# ADC_Isolation.net
KiCad netlist of a schematic drawn in Altium Designer
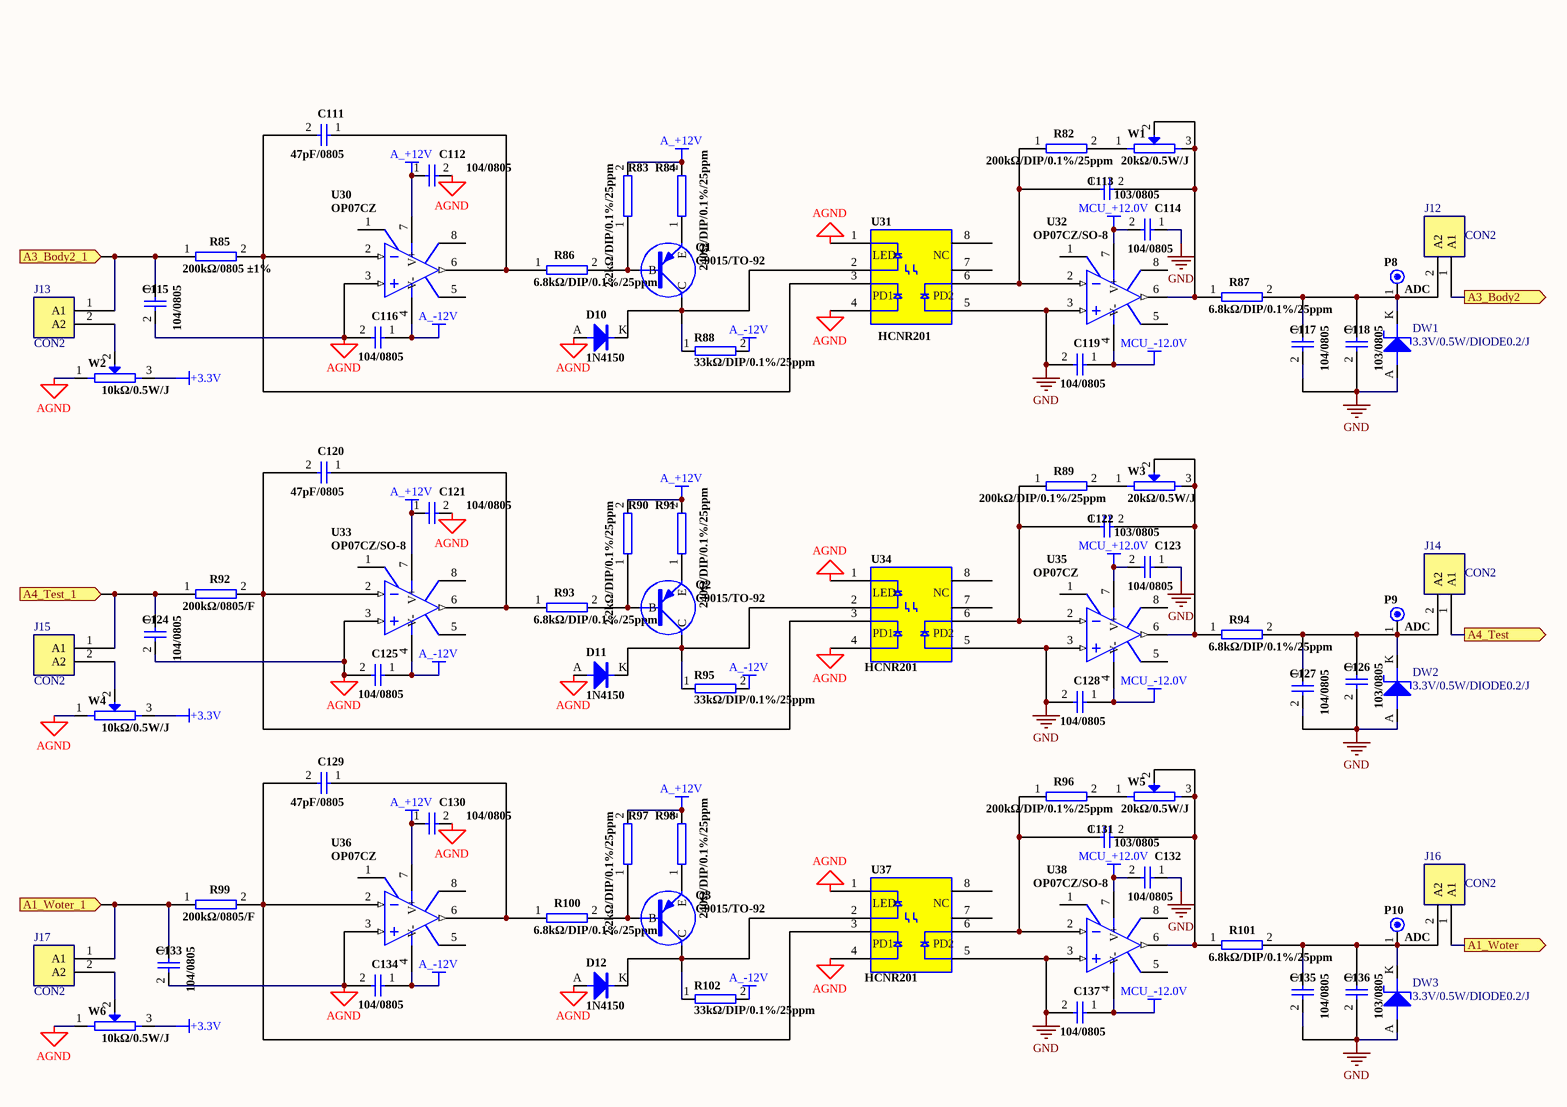
[diagram p0: ADC_Isolation.SchDoc]

(export (version "E")
  (design (tool "Eeschema 10.0.6"))
  (components
    (comp (ref "C111")
      (value "47pF/0805")
      (footprint "C0805")
      (description "贴片电容 47pF/25V ±1% C0805")
      (libsource (lib "") (part "CAP_1"))
    )
    (comp (ref "C112")
      (value "104/0805")
      (footprint "C0805")
      (description "贴片电容 104/25V ±1% C0805")
      (libsource (lib "") (part "CAP_1"))
    )
    (comp (ref "C113")
      (value "103/0805")
      (footprint "C0805")
      (description "贴片电容 103/25V ±1% C0805")
      (libsource (lib "") (part "CAP_1"))
    )
    (comp (ref "C114")
      (value "104/0805")
      (footprint "C0805")
      (description "贴片电容 104/25V ±1% C0805")
      (libsource (lib "") (part "CAP_1"))
    )
    (comp (ref "C115")
      (value "104/0805")
      (footprint "C0805")
      (description "贴片电容 104/25V ±1% C0805")
      (libsource (lib "COOLCONTROL") (part "CAP"))
    )
    (comp (ref "C116")
      (value "104/0805")
      (footprint "COOLCONTROL:C0805")
      (description "贴片电容 104/25V ±1% C0805")
      (libsource (lib "") (part "CAP_1"))
    )
    (comp (ref "C117")
      (value "104/0805")
      (footprint "C0805")
      (description "贴片电容 104/25V ±1% C0805")
      (libsource (lib "COOLCONTROL") (part "CAP"))
    )
    (comp (ref "C118")
      (value "103/0805")
      (footprint "C0805")
      (description "贴片电容 103/25V ±1% C0805")
      (libsource (lib "COOLCONTROL") (part "CAP"))
    )
    (comp (ref "C119")
      (value "104/0805")
      (footprint "C0805")
      (description "贴片电容 104/25V ±1% C0805")
      (libsource (lib "") (part "CAP_1"))
    )
    (comp (ref "C120")
      (value "47pF/0805")
      (footprint "C0805")
      (description "贴片电容 47pF/25V ±1% C0805")
      (libsource (lib "") (part "CAP_1"))
    )
    (comp (ref "C121")
      (value "104/0805")
      (footprint "C0805")
      (description "贴片电容 104/25V ±1% C0805")
      (libsource (lib "") (part "CAP_1"))
    )
    (comp (ref "C122")
      (value "103/0805")
      (footprint "C0805")
      (description "贴片电容 103/25V ±1% C0805")
      (libsource (lib "") (part "CAP_1"))
    )
    (comp (ref "C123")
      (value "104/0805")
      (footprint "C0805")
      (description "贴片电容 104/25V ±1% C0805")
      (libsource (lib "") (part "CAP_1"))
    )
    (comp (ref "C124")
      (value "104/0805")
      (footprint "C0805")
      (description "贴片电容 104/25V ±1% C0805")
      (libsource (lib "COOLCONTROL") (part "CAP"))
    )
    (comp (ref "C125")
      (value "104/0805")
      (footprint "C0805")
      (description "贴片电容 104/25V ±1% C0805")
      (libsource (lib "") (part "CAP_1"))
    )
    (comp (ref "C126")
      (value "103/0805")
      (footprint "COOLCONTROL:C0805")
      (description "贴片电容 103/25V ±1% C0805")
      (libsource (lib "COOLCONTROL") (part "CAP"))
    )
    (comp (ref "C127")
      (value "104/0805")
      (footprint "C0805")
      (description "贴片电容 104/25V ±1% C0805")
      (libsource (lib "COOLCONTROL") (part "CAP"))
    )
    (comp (ref "C128")
      (value "104/0805")
      (footprint "C0805")
      (description "贴片电容 104/25V ±1% C0805")
      (libsource (lib "") (part "CAP_1"))
    )
    (comp (ref "C129")
      (value "47pF/0805")
      (footprint "C0805")
      (description "贴片电容 47pF/25V ±1% C0805")
      (libsource (lib "") (part "CAP_1"))
    )
    (comp (ref "C130")
      (value "104/0805")
      (footprint "C0805")
      (description "贴片电容 104/25V ±1% C0805")
      (libsource (lib "") (part "CAP_1"))
    )
    (comp (ref "C131")
      (value "103/0805")
      (footprint "C0805")
      (description "贴片电容 103/25V ±1% C0805")
      (libsource (lib "") (part "CAP_1"))
    )
    (comp (ref "C132")
      (value "104/0805")
      (footprint "C0805")
      (description "贴片电容 104/25V ±1% C0805")
      (libsource (lib "") (part "CAP_1"))
    )
    (comp (ref "C133")
      (value "104/0805")
      (footprint "C0805")
      (description "贴片电容 104/25V ±1% C0805")
      (libsource (lib "COOLCONTROL") (part "CAP"))
    )
    (comp (ref "C134")
      (value "104/0805")
      (footprint "C0805")
      (description "贴片电容 104/25V ±1% C0805")
      (libsource (lib "") (part "CAP_1"))
    )
    (comp (ref "C135")
      (value "104/0805")
      (footprint "C0805")
      (description "贴片电容 104/25V ±1% C0805")
      (libsource (lib "COOLCONTROL") (part "CAP"))
    )
    (comp (ref "C136")
      (value "103/0805")
      (footprint "COOLCONTROL:C0805")
      (description "贴片电容 103/25V ±1% C0805")
      (libsource (lib "COOLCONTROL") (part "CAP"))
    )
    (comp (ref "C137")
      (value "104/0805")
      (footprint "C0805")
      (description "贴片电容 104/25V ±1% C0805")
      (libsource (lib "") (part "CAP_1"))
    )
    (comp (ref "D10")
      (value "1N4150")
      (footprint "DIODE0.2")
      (description "快速开关二极管 1N415050V 450mA/J /DIODE0.2")
      (libsource (lib "COOLCONTROL") (part "DIODE0"))
    )
    (comp (ref "D11")
      (value "1N4150")
      (footprint "DIODE0.2")
      (description "快速开关二极管 1N415050V 450mA/J /DIODE0.2")
      (libsource (lib "COOLCONTROL") (part "DIODE0"))
    )
    (comp (ref "D12")
      (value "1N4150")
      (footprint "DIODE0.2")
      (description "快速开关二极管 1N415050V 450mA/J /DIODE0.2")
      (libsource (lib "COOLCONTROL") (part "DIODE0"))
    )
    (comp (ref "DW1")
      (value "3.3V/0.5W/DIODE0.2/J")
      (footprint "DIODE0.2")
      (description "稳压二极管 3.3V/0.5W/DIODE0.2/J")
      (libsource (lib "COOLCONTROL") (part "ZENER0"))
    )
    (comp (ref "DW2")
      (value "3.3V/0.5W/DIODE0.2/J")
      (footprint "DIODE0.2")
      (description "稳压二极管 3.3V/0.5W/DIODE0.2/J")
      (libsource (lib "COOLCONTROL") (part "ZENER0"))
    )
    (comp (ref "DW3")
      (value "3.3V/0.5W/DIODE0.2/J")
      (footprint "DIODE0.2")
      (description "稳压二极管 3.3V/0.5W/DIODE0.2/J")
      (libsource (lib "COOLCONTROL") (part "ZENER0"))
    )
    (comp (ref "J12")
      (value "CON2")
      (footprint "COOLCONTROL:2Pin-2.54")
      (description "单排排针（2针）2.54mm 2Pin-2.54")
      (libsource (lib "COOLCONTROL") (part "CON2"))
    )
    (comp (ref "J13")
      (value "CON2")
      (footprint "COOLCONTROL:2Pin-2.54")
      (description "单排排针（2针）2.54mm 2Pin-2.54")
      (libsource (lib "") (part "CON2_1"))
    )
    (comp (ref "J14")
      (value "CON2")
      (footprint "COOLCONTROL:2Pin-2.54")
      (description "单排排针（2针）2.54mm 2Pin-2.54")
      (libsource (lib "COOLCONTROL") (part "CON2"))
    )
    (comp (ref "J15")
      (value "CON2")
      (footprint "COOLCONTROL:2Pin-2.54")
      (description "单排排针（2针）2.54mm 2Pin-2.54")
      (libsource (lib "") (part "CON2_1"))
    )
    (comp (ref "J16")
      (value "CON2")
      (footprint "COOLCONTROL:2Pin-2.54")
      (description "单排排针（2针）2.54mm 2Pin-2.54")
      (libsource (lib "COOLCONTROL") (part "CON2"))
    )
    (comp (ref "J17")
      (value "CON2")
      (footprint "COOLCONTROL:2Pin-2.54")
      (description "单排排针（2针）2.54mm 2Pin-2.54")
      (libsource (lib "") (part "CON2_1"))
    )
    (comp (ref "P8") (value "ADC") (footprint "TESTSMD") (libsource (lib "COOLCONTROL") (part "CON1")))
    (comp (ref "P9") (value "ADC") (footprint "TESTSMD") (libsource (lib "COOLCONTROL") (part "CON1")))
    (comp (ref "P10") (value "ADC") (footprint "TESTSMD") (libsource (lib "COOLCONTROL") (part "CON1")))
    (comp (ref "Q1")
      (value "C9015/TO-92")
      (footprint "COOLCONTROL:TO-92")
      (description "三极管 C9015 TO-92")
      (libsource (lib "COOLCONTROL") (part "PNP"))
    )
    (comp (ref "Q2")
      (value "C9015/TO-92")
      (footprint "COOLCONTROL:TO-92")
      (description "三极管 C9015 TO-92")
      (libsource (lib "COOLCONTROL") (part "PNP"))
    )
    (comp (ref "Q3")
      (value "C9015/TO-92")
      (footprint "COOLCONTROL:TO-92")
      (description "三极管 C9015 TO-92")
      (libsource (lib "COOLCONTROL") (part "PNP"))
    )
    (comp (ref "R82")
      (value "200kΩ/DIP/0.1%/25ppm")
      (footprint "AXIAL0.4")
      (description "高精度电阻 200kΩ DIP ±0.1% 25ppm AXIAL0.4")
      (libsource (lib "COOLCONTROL") (part "RES2"))
    )
    (comp (ref "R83")
      (value "2.2kΩ/DIP/0.1%/25ppm")
      (footprint "AXIAL0.4")
      (description "高精度电阻 2.2kΩ DIP ±0.1% 25ppm AXIAL0.4")
      (libsource (lib "COOLCONTROL") (part "RES2"))
    )
    (comp (ref "R84")
      (value "240Ω/DIP/0.1%/25ppm")
      (footprint "AXIAL0.4")
      (description "高精度电阻 240Ω DIP ±0.1% 25ppm AXIAL0.4")
      (libsource (lib "COOLCONTROL") (part "RES2"))
    )
    (comp (ref "R85")
      (value "200kΩ/0805 ±1%")
      (footprint "R0805")
      (description "贴片电阻 200kΩ 0.25W ±1% R0805")
      (libsource (lib "COOLCONTROL") (part "RES2"))
    )
    (comp (ref "R86")
      (value "6.8kΩ/DIP/0.1%/25ppm")
      (footprint "AXIAL0.4")
      (description "高精度电阻 6.8kΩ DIP ±0.1% 25ppm AXIAL0.4")
      (libsource (lib "COOLCONTROL") (part "RES2"))
    )
    (comp (ref "R87")
      (value "6.8kΩ/DIP/0.1%/25ppm")
      (footprint "AXIAL0.4")
      (description "高精度电阻 6.8kΩ DIP ±0.1% 25ppm AXIAL0.4")
      (libsource (lib "COOLCONTROL") (part "RES2"))
    )
    (comp (ref "R88")
      (value "33kΩ/DIP/0.1%/25ppm")
      (footprint "AXIAL0.4")
      (description "高精度电阻 33kΩ DIP ±0.1% 25ppm AXIAL0.4")
      (libsource (lib "COOLCONTROL") (part "RES2"))
    )
    (comp (ref "R89")
      (value "200kΩ/DIP/0.1%/25ppm")
      (footprint "AXIAL0.4")
      (description "高精度电阻 200kΩ DIP ±0.1% 25ppm AXIAL0.4")
      (libsource (lib "COOLCONTROL") (part "RES2"))
    )
    (comp (ref "R90")
      (value "2.2kΩ/DIP/0.1%/25ppm")
      (footprint "AXIAL0.4")
      (description "高精度电阻 2.2kΩ DIP ±0.1% 25ppm AXIAL0.4")
      (libsource (lib "COOLCONTROL") (part "RES2"))
    )
    (comp (ref "R91")
      (value "240Ω/DIP/0.1%/25ppm")
      (footprint "AXIAL0.4")
      (description "高精度电阻 240Ω DIP ±0.1% 25ppm AXIAL0.4")
      (libsource (lib "COOLCONTROL") (part "RES2"))
    )
    (comp (ref "R92")
      (value "200kΩ/0805/F")
      (footprint "R0805")
      (description "贴片电阻 200kΩ 0.25W ±1% R0805")
      (libsource (lib "COOLCONTROL") (part "RES2"))
    )
    (comp (ref "R93")
      (value "6.8kΩ/DIP/0.1%/25ppm")
      (footprint "AXIAL0.4")
      (description "高精度电阻 6.8kΩ DIP ±0.1% 25ppm AXIAL0.4")
      (libsource (lib "COOLCONTROL") (part "RES2"))
    )
    (comp (ref "R94")
      (value "6.8kΩ/DIP/0.1%/25ppm")
      (footprint "COOLCONTROL:AXIAL0.4")
      (description "高精度电阻 6.8kΩ DIP ±0.1% 25ppm AXIAL0.4")
      (libsource (lib "COOLCONTROL") (part "RES2"))
    )
    (comp (ref "R95")
      (value "33kΩ/DIP/0.1%/25ppm")
      (footprint "AXIAL0.4")
      (description "高精度电阻 33kΩ DIP ±0.1% 25ppm AXIAL0.4")
      (libsource (lib "COOLCONTROL") (part "RES2"))
    )
    (comp (ref "R96")
      (value "200kΩ/DIP/0.1%/25ppm")
      (footprint "AXIAL0.4")
      (description "高精度电阻 200kΩ DIP ±0.1% 25ppm AXIAL0.4")
      (libsource (lib "COOLCONTROL") (part "RES2"))
    )
    (comp (ref "R97")
      (value "2.2kΩ/DIP/0.1%/25ppm")
      (footprint "AXIAL0.4")
      (description "高精度电阻 2.2kΩ DIP ±0.1% 25ppm AXIAL0.4")
      (libsource (lib "COOLCONTROL") (part "RES2"))
    )
    (comp (ref "R98")
      (value "240Ω/DIP/0.1%/25ppm")
      (footprint "AXIAL0.4")
      (description "高精度电阻 240Ω DIP ±0.1% 25ppm AXIAL0.4")
      (libsource (lib "COOLCONTROL") (part "RES2"))
    )
    (comp (ref "R99")
      (value "200kΩ/0805/F")
      (footprint "R0805")
      (description "贴片电阻 200kΩ 0.25W ±1% R0805")
      (libsource (lib "COOLCONTROL") (part "RES2"))
    )
    (comp (ref "R100")
      (value "6.8kΩ/DIP/0.1%/25ppm")
      (footprint "AXIAL0.4")
      (description "高精度电阻 6.8kΩ DIP ±0.1% 25ppm AXIAL0.4")
      (libsource (lib "COOLCONTROL") (part "RES2"))
    )
    (comp (ref "R101")
      (value "6.8kΩ/DIP/0.1%/25ppm")
      (footprint "AXIAL0.4")
      (description "高精度电阻 6.8kΩ DIP ±0.1% 25ppm AXIAL0.4")
      (libsource (lib "COOLCONTROL") (part "RES2"))
    )
    (comp (ref "R102")
      (value "33kΩ/DIP/0.1%/25ppm")
      (footprint "AXIAL0.4")
      (description "高精度电阻 33kΩ DIP ±0.1% 25ppm AXIAL0.4")
      (libsource (lib "COOLCONTROL") (part "RES2"))
    )
    (comp (ref "U30")
      (value "OP07CZ")
      (footprint "SO-8")
      (description "运算放大器 OP07CZ SO-8")
      (libsource (lib "COOLCONTROL") (part "OP07CZ"))
    )
    (comp (ref "U31")
      (value "HCNR201")
      (footprint "DIP08W")
      (description "线性光耦隔离器 HCNR201 DIP08W")
      (libsource (lib "COOLCONTROL") (part "HCNR201"))
    )
    (comp (ref "U32")
      (value "OP07CZ/SO-8")
      (footprint "SO-8")
      (description "运算放大器 OP07CZ SO-8")
      (libsource (lib "COOLCONTROL") (part "OP07CZ"))
    )
    (comp (ref "U33")
      (value "OP07CZ/SO-8")
      (footprint "SO-8")
      (description "运算放大器 OP07CZ SO-8")
      (libsource (lib "COOLCONTROL") (part "OP07CZ"))
    )
    (comp (ref "U34")
      (value "HCNR201")
      (footprint "DIP08W")
      (description "线性光耦隔离器 HCNR201 DIP08W")
      (libsource (lib "COOLCONTROL") (part "HCNR201"))
    )
    (comp (ref "U35")
      (value "OP07CZ")
      (footprint "SO-8")
      (description "运算放大器 OP07CZ SO-8")
      (libsource (lib "COOLCONTROL") (part "OP07CZ"))
    )
    (comp (ref "U36")
      (value "OP07CZ")
      (footprint "SO-8")
      (description "运算放大器 OP07CZ SO-8")
      (libsource (lib "COOLCONTROL") (part "OP07CZ"))
    )
    (comp (ref "U37")
      (value "HCNR201")
      (footprint "DIP08W")
      (description "线性光耦隔离器 HCNR201 DIP08W")
      (libsource (lib "COOLCONTROL") (part "HCNR201"))
    )
    (comp (ref "U38")
      (value "OP07CZ/SO-8")
      (footprint "SO-8")
      (description "运算放大器 OP07CZ SO-8")
      (libsource (lib "COOLCONTROL") (part "OP07CZ"))
    )
    (comp (ref "W1")
      (value "20kΩ/0.5W/J")
      (footprint "3224W")
      (description "高精密可调电位器 20kΩ/0.5W/J  3224W")
      (libsource (lib "COOLCONTROL") (part "RPOT"))
    )
    (comp (ref "W2")
      (value "10kΩ/0.5W/J")
      (footprint "3224W")
      (description "高精密可调电位器 10kΩ/0.5W/J  3224W")
      (libsource (lib "COOLCONTROL") (part "RPOT"))
    )
    (comp (ref "W3")
      (value "20kΩ/0.5W/J")
      (footprint "3224W")
      (description "高精密可调电位器 20kΩ/0.5W/J  3224W")
      (libsource (lib "COOLCONTROL") (part "RPOT"))
    )
    (comp (ref "W4")
      (value "10kΩ/0.5W/J")
      (footprint "3224W")
      (description "高精密可调电位器 10kΩ/0.5W/J  3224W")
      (libsource (lib "COOLCONTROL") (part "RPOT"))
    )
    (comp (ref "W5")
      (value "20kΩ/0.5W/J")
      (footprint "3224W")
      (description "高精密可调电位器 20kΩ/0.5W/J  3224W")
      (libsource (lib "COOLCONTROL") (part "RPOT"))
    )
    (comp (ref "W6")
      (value "10kΩ/0.5W/J")
      (footprint "3224W")
      (description "高精密可调电位器 10kΩ/0.5W/J  3224W")
      (libsource (lib "COOLCONTROL") (part "RPOT"))
    )
  )
  (nets
    (net (code "1") (name "+3.3V") (class "Default")
      (node (ref "W2") (pin "3") (pintype "passive"))
      (node (ref "W4") (pin "3") (pintype "passive"))
      (node (ref "W6") (pin "3") (pintype "passive"))
    )
    (net (code "2") (name "/A1_Woter") (class "Default")
      (node (ref "J16") (pin "1") (pinfunction "A1_1") (pintype "passive"))
    )
    (net (code "3") (name "/A1_Woter_1") (class "Default")
      (node (ref "C133") (pin "1") (pintype "passive"))
      (node (ref "J17") (pin "1") (pinfunction "A1_1") (pintype "passive"))
      (node (ref "R99") (pin "1") (pintype "passive"))
    )
    (net (code "4") (name "/A3_Body2") (class "Default")
      (node (ref "J12") (pin "1") (pinfunction "A1_1") (pintype "passive"))
    )
    (net (code "5") (name "/A3_Body2_1") (class "Default")
      (node (ref "C115") (pin "1") (pintype "passive"))
      (node (ref "J13") (pin "1") (pinfunction "A1_1") (pintype "passive"))
      (node (ref "R85") (pin "1") (pintype "passive"))
    )
    (net (code "6") (name "/A4_Test") (class "Default")
      (node (ref "J14") (pin "1") (pinfunction "A1_1") (pintype "passive"))
    )
    (net (code "7") (name "/A4_Test_1") (class "Default")
      (node (ref "C124") (pin "1") (pintype "passive"))
      (node (ref "J15") (pin "1") (pinfunction "A1_1") (pintype "passive"))
      (node (ref "R92") (pin "1") (pintype "passive"))
    )
    (net (code "8") (name "AGND") (class "Default")
      (node (ref "C112") (pin "2") (pintype "passive"))
      (node (ref "C115") (pin "2") (pintype "passive"))
      (node (ref "C116") (pin "2") (pintype "passive"))
      (node (ref "C121") (pin "2") (pintype "passive"))
      (node (ref "C124") (pin "2") (pintype "passive"))
      (node (ref "C125") (pin "2") (pintype "passive"))
      (node (ref "C130") (pin "2") (pintype "passive"))
      (node (ref "C133") (pin "2") (pintype "passive"))
      (node (ref "C134") (pin "2") (pintype "passive"))
      (node (ref "D10") (pin "A") (pintype "passive"))
      (node (ref "D11") (pin "A") (pintype "passive"))
      (node (ref "D12") (pin "A") (pintype "passive"))
      (node (ref "U30") (pin "3") (pintype "input"))
      (node (ref "U31") (pin "1") (pintype "passive"))
      (node (ref "U31") (pin "4") (pintype "passive"))
      (node (ref "U33") (pin "3") (pintype "input"))
      (node (ref "U34") (pin "1") (pintype "passive"))
      (node (ref "U34") (pin "4") (pintype "passive"))
      (node (ref "U36") (pin "3") (pintype "input"))
      (node (ref "U37") (pin "1") (pintype "passive"))
      (node (ref "U37") (pin "4") (pintype "passive"))
      (node (ref "W2") (pin "1") (pintype "passive"))
      (node (ref "W4") (pin "1") (pintype "passive"))
      (node (ref "W6") (pin "1") (pintype "passive"))
    )
    (net (code "9") (name "A_+12V") (class "Default")
      (node (ref "C112") (pin "1") (pintype "passive"))
      (node (ref "C121") (pin "1") (pintype "passive"))
      (node (ref "C130") (pin "1") (pintype "passive"))
      (node (ref "R83") (pin "2") (pintype "passive"))
      (node (ref "R84") (pin "2") (pintype "passive"))
      (node (ref "R90") (pin "2") (pintype "passive"))
      (node (ref "R91") (pin "2") (pintype "passive"))
      (node (ref "R97") (pin "2") (pintype "passive"))
      (node (ref "R98") (pin "2") (pintype "passive"))
      (node (ref "U30") (pin "7") (pinfunction "V+_7") (pintype "power_in"))
      (node (ref "U33") (pin "7") (pinfunction "V+_7") (pintype "power_in"))
      (node (ref "U36") (pin "7") (pinfunction "V+_7") (pintype "power_in"))
    )
    (net (code "10") (name "A_-12V") (class "Default")
      (node (ref "C116") (pin "1") (pintype "passive"))
      (node (ref "C125") (pin "1") (pintype "passive"))
      (node (ref "C134") (pin "1") (pintype "passive"))
      (node (ref "R102") (pin "2") (pintype "passive"))
      (node (ref "R88") (pin "2") (pintype "passive"))
      (node (ref "R95") (pin "2") (pintype "passive"))
      (node (ref "U30") (pin "4") (pinfunction "V-_4") (pintype "power_in"))
      (node (ref "U33") (pin "4") (pinfunction "V-_4") (pintype "power_in"))
      (node (ref "U36") (pin "4") (pinfunction "V-_4") (pintype "power_in"))
    )
    (net (code "11") (name "GND") (class "Default")
      (node (ref "C114") (pin "1") (pintype "passive"))
      (node (ref "C117") (pin "2") (pintype "passive"))
      (node (ref "C118") (pin "2") (pintype "passive"))
      (node (ref "C119") (pin "2") (pintype "passive"))
      (node (ref "C123") (pin "1") (pintype "passive"))
      (node (ref "C126") (pin "2") (pintype "passive"))
      (node (ref "C127") (pin "2") (pintype "passive"))
      (node (ref "C128") (pin "2") (pintype "passive"))
      (node (ref "C132") (pin "1") (pintype "passive"))
      (node (ref "C135") (pin "2") (pintype "passive"))
      (node (ref "C136") (pin "2") (pintype "passive"))
      (node (ref "C137") (pin "2") (pintype "passive"))
      (node (ref "DW1") (pin "A") (pintype "passive"))
      (node (ref "DW2") (pin "A") (pintype "passive"))
      (node (ref "DW3") (pin "A") (pintype "passive"))
      (node (ref "U31") (pin "5") (pintype "passive"))
      (node (ref "U32") (pin "3") (pintype "input"))
      (node (ref "U34") (pin "5") (pintype "passive"))
      (node (ref "U35") (pin "3") (pintype "input"))
      (node (ref "U37") (pin "5") (pintype "passive"))
      (node (ref "U38") (pin "3") (pintype "input"))
    )
    (net (code "12") (name "MCU_+12.0V") (class "Default")
      (node (ref "C114") (pin "2") (pintype "passive"))
      (node (ref "C123") (pin "2") (pintype "passive"))
      (node (ref "C132") (pin "2") (pintype "passive"))
      (node (ref "U32") (pin "7") (pinfunction "V+_7") (pintype "power_in"))
      (node (ref "U35") (pin "7") (pinfunction "V+_7") (pintype "power_in"))
      (node (ref "U38") (pin "7") (pinfunction "V+_7") (pintype "power_in"))
    )
    (net (code "13") (name "MCU_-12.0V") (class "Default")
      (node (ref "C119") (pin "1") (pintype "passive"))
      (node (ref "C128") (pin "1") (pintype "passive"))
      (node (ref "C137") (pin "1") (pintype "passive"))
      (node (ref "U32") (pin "4") (pinfunction "V-_4") (pintype "power_in"))
      (node (ref "U35") (pin "4") (pinfunction "V-_4") (pintype "power_in"))
      (node (ref "U38") (pin "4") (pinfunction "V-_4") (pintype "power_in"))
    )
    (net (code "14") (name "Net-(C111-Pad1)") (class "Default")
      (node (ref "C111") (pin "1") (pintype "passive"))
      (node (ref "R86") (pin "1") (pintype "passive"))
      (node (ref "U30") (pin "6") (pintype "output"))
    )
    (net (code "15") (name "Net-(C111-Pad2)") (class "Default")
      (node (ref "C111") (pin "2") (pintype "passive"))
      (node (ref "R85") (pin "2") (pintype "passive"))
      (node (ref "U30") (pin "2") (pintype "input"))
      (node (ref "U31") (pin "3") (pintype "passive"))
    )
    (net (code "16") (name "Net-(C113-Pad1)") (class "Default")
      (node (ref "C113") (pin "1") (pintype "passive"))
      (node (ref "R82") (pin "1") (pintype "passive"))
      (node (ref "U31") (pin "6") (pintype "passive"))
      (node (ref "U32") (pin "2") (pintype "input"))
    )
    (net (code "17") (name "Net-(C113-Pad2)") (class "Default")
      (node (ref "C113") (pin "2") (pintype "passive"))
      (node (ref "R87") (pin "1") (pintype "passive"))
      (node (ref "U32") (pin "6") (pintype "output"))
      (node (ref "W1") (pin "2") (pintype "passive"))
      (node (ref "W1") (pin "3") (pintype "passive"))
    )
    (net (code "18") (name "Net-(C120-Pad1)") (class "Default")
      (node (ref "C120") (pin "1") (pintype "passive"))
      (node (ref "R93") (pin "1") (pintype "passive"))
      (node (ref "U33") (pin "6") (pintype "output"))
    )
    (net (code "19") (name "Net-(C120-Pad2)") (class "Default")
      (node (ref "C120") (pin "2") (pintype "passive"))
      (node (ref "R92") (pin "2") (pintype "passive"))
      (node (ref "U33") (pin "2") (pintype "input"))
      (node (ref "U34") (pin "3") (pintype "passive"))
    )
    (net (code "20") (name "Net-(C122-Pad1)") (class "Default")
      (node (ref "C122") (pin "1") (pintype "passive"))
      (node (ref "R89") (pin "1") (pintype "passive"))
      (node (ref "U34") (pin "6") (pintype "passive"))
      (node (ref "U35") (pin "2") (pintype "input"))
    )
    (net (code "21") (name "Net-(C122-Pad2)") (class "Default")
      (node (ref "C122") (pin "2") (pintype "passive"))
      (node (ref "R94") (pin "1") (pintype "passive"))
      (node (ref "U35") (pin "6") (pintype "output"))
      (node (ref "W3") (pin "2") (pintype "passive"))
      (node (ref "W3") (pin "3") (pintype "passive"))
    )
    (net (code "22") (name "Net-(C129-Pad1)") (class "Default")
      (node (ref "C129") (pin "1") (pintype "passive"))
      (node (ref "R100") (pin "1") (pintype "passive"))
      (node (ref "U36") (pin "6") (pintype "output"))
    )
    (net (code "23") (name "Net-(C129-Pad2)") (class "Default")
      (node (ref "C129") (pin "2") (pintype "passive"))
      (node (ref "R99") (pin "2") (pintype "passive"))
      (node (ref "U36") (pin "2") (pintype "input"))
      (node (ref "U37") (pin "3") (pintype "passive"))
    )
    (net (code "24") (name "Net-(C131-Pad1)") (class "Default")
      (node (ref "C131") (pin "1") (pintype "passive"))
      (node (ref "R96") (pin "1") (pintype "passive"))
      (node (ref "U37") (pin "6") (pintype "passive"))
      (node (ref "U38") (pin "2") (pintype "input"))
    )
    (net (code "25") (name "Net-(C131-Pad2)") (class "Default")
      (node (ref "C131") (pin "2") (pintype "passive"))
      (node (ref "R101") (pin "1") (pintype "passive"))
      (node (ref "U38") (pin "6") (pintype "output"))
      (node (ref "W5") (pin "2") (pintype "passive"))
      (node (ref "W5") (pin "3") (pintype "passive"))
    )
    (net (code "26") (name "Net-(J12-A2)") (class "Default")
      (node (ref "C117") (pin "1") (pintype "passive"))
      (node (ref "C118") (pin "1") (pintype "passive"))
      (node (ref "DW1") (pin "K") (pintype "passive"))
      (node (ref "J12") (pin "2") (pinfunction "A2_2") (pintype "passive"))
      (node (ref "P8") (pin "1") (pintype "passive"))
      (node (ref "R87") (pin "2") (pintype "passive"))
    )
    (net (code "27") (name "Net-(J13-A2)") (class "Default")
      (node (ref "J13") (pin "2") (pinfunction "A2_2") (pintype "passive"))
      (node (ref "W2") (pin "2") (pintype "passive"))
    )
    (net (code "28") (name "Net-(J14-A2)") (class "Default")
      (node (ref "C126") (pin "1") (pintype "passive"))
      (node (ref "C127") (pin "1") (pintype "passive"))
      (node (ref "DW2") (pin "K") (pintype "passive"))
      (node (ref "J14") (pin "2") (pinfunction "A2_2") (pintype "passive"))
      (node (ref "P9") (pin "1") (pintype "passive"))
      (node (ref "R94") (pin "2") (pintype "passive"))
    )
    (net (code "29") (name "Net-(J15-A2)") (class "Default")
      (node (ref "J15") (pin "2") (pinfunction "A2_2") (pintype "passive"))
      (node (ref "W4") (pin "2") (pintype "passive"))
    )
    (net (code "30") (name "Net-(J16-A2)") (class "Default")
      (node (ref "C135") (pin "1") (pintype "passive"))
      (node (ref "C136") (pin "1") (pintype "passive"))
      (node (ref "DW3") (pin "K") (pintype "passive"))
      (node (ref "J16") (pin "2") (pinfunction "A2_2") (pintype "passive"))
      (node (ref "P10") (pin "1") (pintype "passive"))
      (node (ref "R101") (pin "2") (pintype "passive"))
    )
    (net (code "31") (name "Net-(J17-A2)") (class "Default")
      (node (ref "J17") (pin "2") (pinfunction "A2_2") (pintype "passive"))
      (node (ref "W6") (pin "2") (pintype "passive"))
    )
    (net (code "32") (name "Net-(Q1-B)") (class "Default")
      (node (ref "Q1") (pin "1") (pinfunction "B_1") (pintype "passive"))
      (node (ref "R83") (pin "1") (pintype "passive"))
      (node (ref "R86") (pin "2") (pintype "passive"))
    )
    (net (code "33") (name "Net-(Q1-C)") (class "Default")
      (node (ref "D10") (pin "K") (pintype "passive"))
      (node (ref "Q1") (pin "3") (pinfunction "C_3") (pintype "passive"))
      (node (ref "R88") (pin "1") (pintype "passive"))
      (node (ref "U31") (pin "2") (pintype "passive"))
    )
    (net (code "34") (name "Net-(Q1-E)") (class "Default")
      (node (ref "Q1") (pin "2") (pinfunction "E_2") (pintype "passive"))
      (node (ref "R84") (pin "1") (pintype "passive"))
    )
    (net (code "35") (name "Net-(Q2-B)") (class "Default")
      (node (ref "Q2") (pin "1") (pinfunction "B_1") (pintype "passive"))
      (node (ref "R90") (pin "1") (pintype "passive"))
      (node (ref "R93") (pin "2") (pintype "passive"))
    )
    (net (code "36") (name "Net-(Q2-C)") (class "Default")
      (node (ref "D11") (pin "K") (pintype "passive"))
      (node (ref "Q2") (pin "3") (pinfunction "C_3") (pintype "passive"))
      (node (ref "R95") (pin "1") (pintype "passive"))
      (node (ref "U34") (pin "2") (pintype "passive"))
    )
    (net (code "37") (name "Net-(Q2-E)") (class "Default")
      (node (ref "Q2") (pin "2") (pinfunction "E_2") (pintype "passive"))
      (node (ref "R91") (pin "1") (pintype "passive"))
    )
    (net (code "38") (name "Net-(Q3-B)") (class "Default")
      (node (ref "Q3") (pin "1") (pinfunction "B_1") (pintype "passive"))
      (node (ref "R100") (pin "2") (pintype "passive"))
      (node (ref "R97") (pin "1") (pintype "passive"))
    )
    (net (code "39") (name "Net-(Q3-C)") (class "Default")
      (node (ref "D12") (pin "K") (pintype "passive"))
      (node (ref "Q3") (pin "3") (pinfunction "C_3") (pintype "passive"))
      (node (ref "R102") (pin "1") (pintype "passive"))
      (node (ref "U37") (pin "2") (pintype "passive"))
    )
    (net (code "40") (name "Net-(Q3-E)") (class "Default")
      (node (ref "Q3") (pin "2") (pinfunction "E_2") (pintype "passive"))
      (node (ref "R98") (pin "1") (pintype "passive"))
    )
    (net (code "41") (name "Net-(R82-Pad2)") (class "Default")
      (node (ref "R82") (pin "2") (pintype "passive"))
      (node (ref "W1") (pin "1") (pintype "passive"))
    )
    (net (code "42") (name "Net-(R89-Pad2)") (class "Default")
      (node (ref "R89") (pin "2") (pintype "passive"))
      (node (ref "W3") (pin "1") (pintype "passive"))
    )
    (net (code "43") (name "Net-(R96-Pad2)") (class "Default")
      (node (ref "R96") (pin "2") (pintype "passive"))
      (node (ref "W5") (pin "1") (pintype "passive"))
    )
    (net (code "44") (name "unconnected-(U30-Pad1)") (class "Default")
      (node (ref "U30") (pin "1") (pintype "passive"))
    )
    (net (code "45") (name "unconnected-(U30-Pad5)") (class "Default")
      (node (ref "U30") (pin "5") (pintype "passive"))
    )
    (net (code "46") (name "unconnected-(U30-Pad8)") (class "Default")
      (node (ref "U30") (pin "8") (pintype "passive"))
    )
    (net (code "47") (name "unconnected-(U31-Pad7)") (class "Default")
      (node (ref "U31") (pin "7") (pintype "passive"))
    )
    (net (code "48") (name "unconnected-(U31-Pad8)") (class "Default")
      (node (ref "U31") (pin "8") (pintype "passive"))
    )
    (net (code "49") (name "unconnected-(U32-Pad1)") (class "Default")
      (node (ref "U32") (pin "1") (pintype "passive"))
    )
    (net (code "50") (name "unconnected-(U32-Pad5)") (class "Default")
      (node (ref "U32") (pin "5") (pintype "passive"))
    )
    (net (code "51") (name "unconnected-(U32-Pad8)") (class "Default")
      (node (ref "U32") (pin "8") (pintype "passive"))
    )
    (net (code "52") (name "unconnected-(U33-Pad1)") (class "Default")
      (node (ref "U33") (pin "1") (pintype "passive"))
    )
    (net (code "53") (name "unconnected-(U33-Pad5)") (class "Default")
      (node (ref "U33") (pin "5") (pintype "passive"))
    )
    (net (code "54") (name "unconnected-(U33-Pad8)") (class "Default")
      (node (ref "U33") (pin "8") (pintype "passive"))
    )
    (net (code "55") (name "unconnected-(U34-Pad7)") (class "Default")
      (node (ref "U34") (pin "7") (pintype "passive"))
    )
    (net (code "56") (name "unconnected-(U34-Pad8)") (class "Default")
      (node (ref "U34") (pin "8") (pintype "passive"))
    )
    (net (code "57") (name "unconnected-(U35-Pad1)") (class "Default")
      (node (ref "U35") (pin "1") (pintype "passive"))
    )
    (net (code "58") (name "unconnected-(U35-Pad5)") (class "Default")
      (node (ref "U35") (pin "5") (pintype "passive"))
    )
    (net (code "59") (name "unconnected-(U35-Pad8)") (class "Default")
      (node (ref "U35") (pin "8") (pintype "passive"))
    )
    (net (code "60") (name "unconnected-(U36-Pad1)") (class "Default")
      (node (ref "U36") (pin "1") (pintype "passive"))
    )
    (net (code "61") (name "unconnected-(U36-Pad5)") (class "Default")
      (node (ref "U36") (pin "5") (pintype "passive"))
    )
    (net (code "62") (name "unconnected-(U36-Pad8)") (class "Default")
      (node (ref "U36") (pin "8") (pintype "passive"))
    )
    (net (code "63") (name "unconnected-(U37-Pad7)") (class "Default")
      (node (ref "U37") (pin "7") (pintype "passive"))
    )
    (net (code "64") (name "unconnected-(U37-Pad8)") (class "Default")
      (node (ref "U37") (pin "8") (pintype "passive"))
    )
    (net (code "65") (name "unconnected-(U38-Pad1)") (class "Default")
      (node (ref "U38") (pin "1") (pintype "passive"))
    )
    (net (code "66") (name "unconnected-(U38-Pad5)") (class "Default")
      (node (ref "U38") (pin "5") (pintype "passive"))
    )
    (net (code "67") (name "unconnected-(U38-Pad8)") (class "Default")
      (node (ref "U38") (pin "8") (pintype "passive"))
    )
  )
)
